# wi-fi.net
KiCad netlist of a schematic drawn in Altium Designer
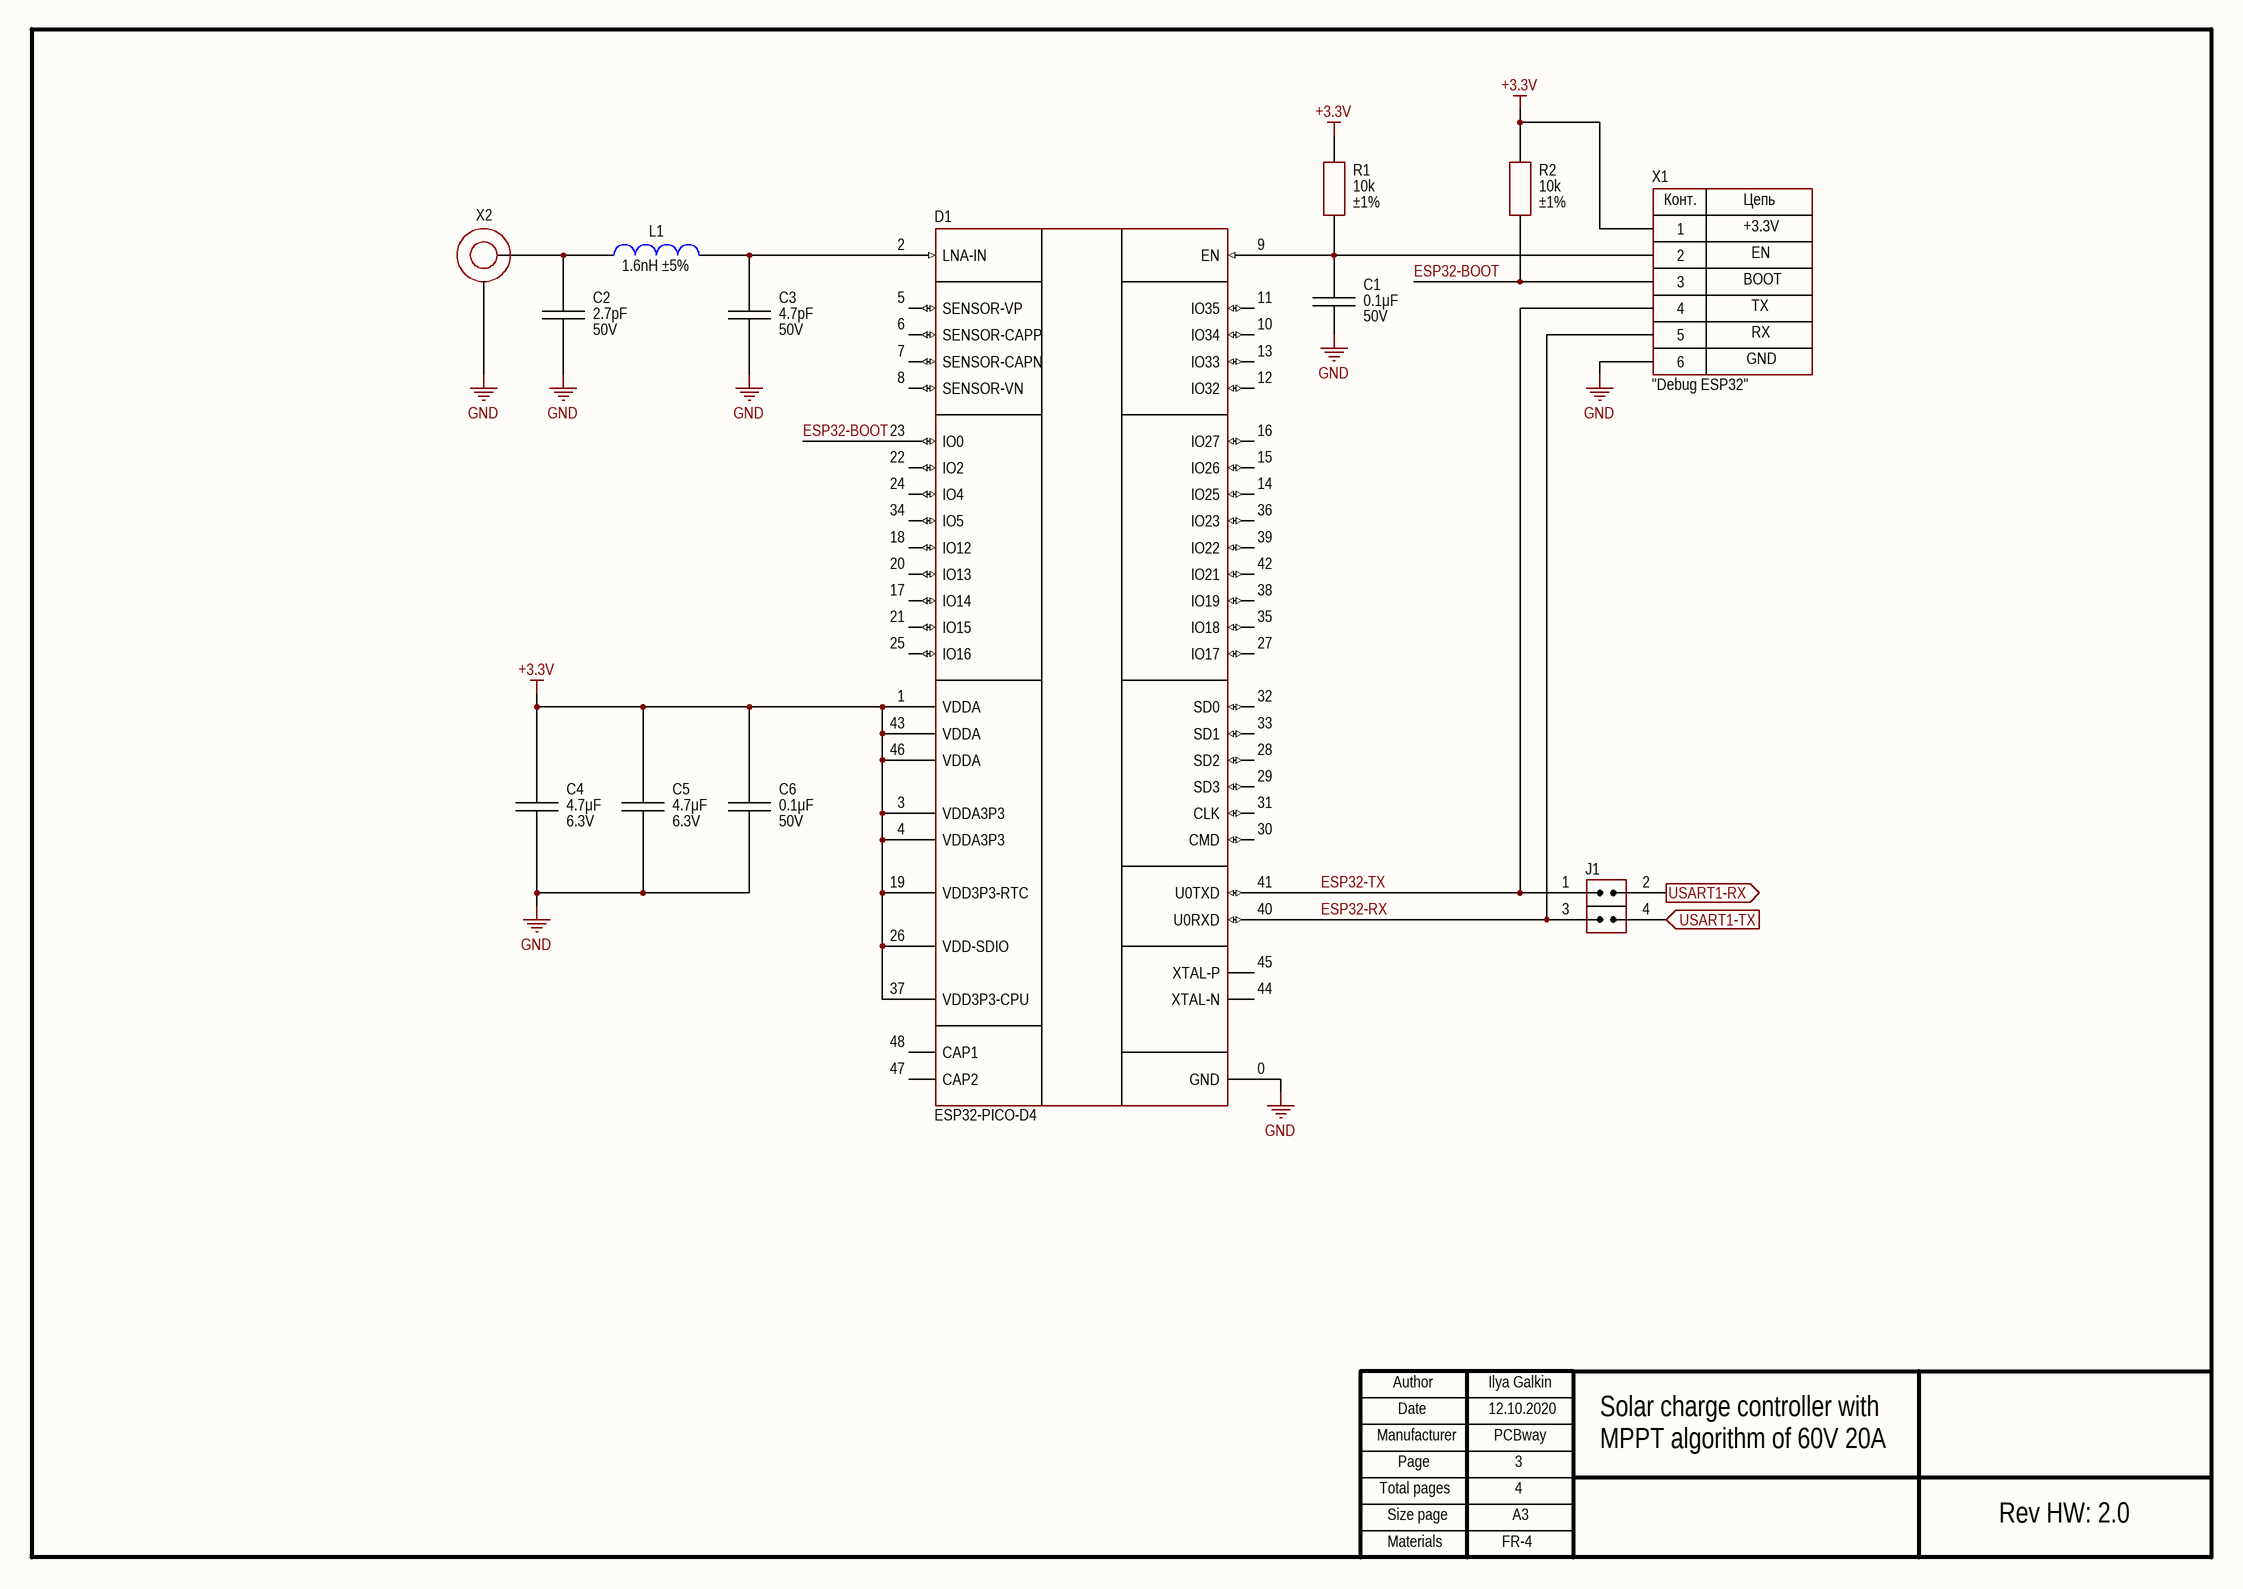
[diagram p0: wi-fi.SchDoc]

(export (version "E")
  (design (tool "Eeschema 10.0.6"))
  (components
    (comp (ref "C1")
      (value "0.1μF")
      (footprint "CAP: 0603")
      (fields
        (field (name "MANUFACTURER") "Samsung")
        (field (name "PARTNUMBER") "CL10B104KB8WPND")
        (field (name "VALUEMANUFACTURERPARTNUMBER") "Ceramic capacitor, 0.1μF, X7R, ±10%, 50V, 0603, -55...+125°C")
        (field (name "VOLTAGE") "50V")
      )
      (libsource (lib "Capacitor") (part "Ceramic_0603"))
    )
    (comp (ref "C2")
      (value "2.7pF")
      (footprint "CAP: 0603")
      (fields
        (field (name "MANUFACTURER") "Samsung")
        (field (name "PARTNUMBER") "CL10C2R7CB81PNC")
        (field (name "VALUEMANUFACTURERPARTNUMBER") "Ceramic capacitor, 2.7pF, NPO, ±0.25pF, 50V, 0603, -55...+125°C")
        (field (name "VOLTAGE") "50V")
      )
      (libsource (lib "capacitor") (part "Ceramic_0603"))
    )
    (comp (ref "C3")
      (value "4.7pF")
      (footprint "CAP: 0603")
      (fields
        (field (name "MANUFACTURER") "Samsung")
        (field (name "PARTNUMBER") "CL10C4R7BB8NNNC")
        (field (name "VALUEMANUFACTURERPARTNUMBER") "Ceramic capacitor, 4.7pF, NPO, ±0.1pF, 50V, 0603, -55...+125°C")
        (field (name "VOLTAGE") "50V")
      )
      (libsource (lib "capacitor") (part "Ceramic_0603"))
    )
    (comp (ref "C4")
      (value "4.7μF")
      (footprint "CAP: 0603")
      (fields
        (field (name "MANUFACTURER") "Samsung")
        (field (name "PARTNUMBER") "CL10B475KQ8NQNC")
        (field (name "VALUEMANUFACTURERPARTNUMBER") "Ceramic capacitor, 4.7μF, X7R, ±10%, 6.3V, 0603, -55...+125°C")
        (field (name "VOLTAGE") "6.3V")
      )
      (libsource (lib "Capacitor") (part "Ceramic_0603"))
    )
    (comp (ref "C5")
      (value "4.7μF")
      (footprint "CAP: 0603")
      (fields
        (field (name "MANUFACTURER") "Samsung")
        (field (name "PARTNUMBER") "CL10B475KQ8NQNC")
        (field (name "VALUEMANUFACTURERPARTNUMBER") "Ceramic capacitor, 4.7μF, X7R, ±10%, 6.3V, 0603, -55...+125°C")
        (field (name "VOLTAGE") "6.3V")
      )
      (libsource (lib "Capacitor") (part "Ceramic_0603"))
    )
    (comp (ref "C6")
      (value "0.1μF")
      (footprint "CAP: 0603")
      (fields
        (field (name "MANUFACTURER") "Samsung")
        (field (name "PARTNUMBER") "CL10B104KB8WPND")
        (field (name "VALUEMANUFACTURERPARTNUMBER") "Ceramic capacitor, 0.1μF, X7R, ±10%, 50V, 0603, -55...+125°C")
        (field (name "VOLTAGE") "50V")
      )
      (libsource (lib "Capacitor") (part "Ceramic_0603"))
    )
    (comp (ref "D1")
      (value "~")
      (footprint "48-LGA (7x7)")
      (description "Wi-Fi+BT")
      (fields (field (name "MANUFACTURER") "Espressif Systems") (field (name "PARTNUMBER") "ESP32-PICO-D4"))
      (libsource (lib "ic-rf-transceiver") (part "ESP32-PICO-D4"))
    )
    (comp (ref "J1")
      (value "~")
      (footprint "CON: JUMPER x2")
      (libsource (lib "connector") (part "Jumper_double"))
    )
    (comp (ref "L1")
      (value "1.6nH")
      (footprint "IND: 0603")
      (fields
        (field (name "MANUFACTURER") "Murata Electronics")
        (field (name "PARTNUMBER") "LQW18AS1N6J0ZD")
        (field (name "VALUEMANUFACTURERPARTNUMBER") "Fixed inductor, 1.6nH, ±5%, 0603, 700mA, -55...+125°C")
        (field (name "TOLERANCE") "±5%")
      )
      (libsource (lib "inductor") (part "Inductor_0603"))
    )
    (comp (ref "R1")
      (value "10k")
      (footprint "RES: 0603")
      (fields
        (field (name "MANUFACTURER") "Yageo")
        (field (name "PARTNUMBER") "AC0603FR-0710KL")
        (field (name "VALUEMANUFACTURERPARTNUMBER") "Resistor film, 10k, ±1%, 0603, 0.1W, -55...+125°C")
        (field (name "TOLERANCE") "±1%")
      )
      (libsource (lib "Resistor") (part "Resistor_0603"))
    )
    (comp (ref "R2")
      (value "10k")
      (footprint "RES: 0603")
      (fields
        (field (name "MANUFACTURER") "Yageo")
        (field (name "PARTNUMBER") "AC0603FR-0710KL")
        (field (name "VALUEMANUFACTURERPARTNUMBER") "Resistor film, 10k, ±1%, 0603, 0.1W, -55...+125°C")
        (field (name "TOLERANCE") "±1%")
      )
      (libsource (lib "Resistor") (part "Resistor_0603"))
    )
    (comp (ref "X1")
      (value "~")
      (footprint "CON: SM06B-GHS")
      (fields
        (field (name "MANUFACTURER") "JST")
        (field (name "VALUEMANUFACTURERPARTNUMBER") "Connector, 6pin, 1.25mm, 50VDC, 1A")
        (field (name "PARTNUMBER") "SM06B-GHS")
        (field (name "COMMENTTEXT") "\"Debug ESP32\"")
      )
      (libsource (lib "connector") (part "Connector_SM06B"))
    )
    (comp (ref "X2")
      (value "~")
      (footprint "CON: SMA")
      (fields
        (field (name "MANUFACTURER") "TE Connectivity")
        (field (name "VALUEMANUFACTURERPARTNUMBER") "Connector SMA, 50 Ohm, 3GHz")
        (field (name "PARTNUMBER") "5-1814832-1")
      )
      (libsource (lib "connector") (part "Connector_SMA"))
    )
  )
  (nets
    (net (code "1") (name "+3.3V") (class "Default")
      (node (ref "C4") (pin "2") (pinfunction "2_2") (pintype "power_in"))
      (node (ref "C5") (pin "2") (pinfunction "2_2") (pintype "power_in"))
      (node (ref "C6") (pin "2") (pinfunction "2_2") (pintype "power_in"))
      (node (ref "D1") (pin "1") (pinfunction "VDDA_1") (pintype "passive"))
      (node (ref "D1") (pin "19") (pinfunction "VDD3P3-RTC_19") (pintype "passive"))
      (node (ref "D1") (pin "26") (pinfunction "VDD-SDIO_26") (pintype "passive"))
      (node (ref "D1") (pin "3") (pinfunction "VDDA3P3_3") (pintype "passive"))
      (node (ref "D1") (pin "37") (pinfunction "VDD3P3-CPU_37") (pintype "passive"))
      (node (ref "D1") (pin "4") (pinfunction "VDDA3P3_4") (pintype "passive"))
      (node (ref "D1") (pin "43") (pinfunction "VDDA_43") (pintype "passive"))
      (node (ref "D1") (pin "46") (pinfunction "VDDA_46") (pintype "passive"))
      (node (ref "R1") (pin "2") (pinfunction "2_2") (pintype "passive"))
      (node (ref "R2") (pin "2") (pinfunction "2_2") (pintype "passive"))
      (node (ref "X1") (pin "1") (pinfunction "1_1") (pintype "passive"))
    )
    (net (code "2") (name "/ESP32-BOOT") (class "Default")
      (node (ref "D1") (pin "23") (pinfunction "IO0_23") (pintype "bidirectional"))
      (node (ref "R2") (pin "1") (pinfunction "1_1") (pintype "passive"))
      (node (ref "X1") (pin "3") (pinfunction "3_3") (pintype "power_in"))
    )
    (net (code "3") (name "/ESP32-RX") (class "Default")
      (node (ref "D1") (pin "40") (pinfunction "U0RXD_40") (pintype "bidirectional"))
      (node (ref "J1") (pin "3") (pinfunction "IN_3") (pintype "passive"))
      (node (ref "X1") (pin "5") (pinfunction "5_5") (pintype "power_in"))
    )
    (net (code "4") (name "/ESP32-TX") (class "Default")
      (node (ref "D1") (pin "41") (pinfunction "U0TXD_41") (pintype "bidirectional"))
      (node (ref "J1") (pin "1") (pinfunction "IN_1") (pintype "passive"))
      (node (ref "X1") (pin "4") (pinfunction "4_4") (pintype "power_in"))
    )
    (net (code "5") (name "/USART1-RX") (class "Default")
      (node (ref "J1") (pin "2") (pinfunction "IN_2") (pintype "passive"))
    )
    (net (code "6") (name "/USART1-TX") (class "Default")
      (node (ref "J1") (pin "4") (pinfunction "IN_4") (pintype "passive"))
    )
    (net (code "7") (name "GND") (class "Default")
      (node (ref "C1") (pin "1") (pinfunction "1_1") (pintype "power_in"))
      (node (ref "C2") (pin "1") (pinfunction "1_1") (pintype "passive"))
      (node (ref "C3") (pin "1") (pinfunction "1_1") (pintype "passive"))
      (node (ref "C4") (pin "1") (pinfunction "1_1") (pintype "power_in"))
      (node (ref "C5") (pin "1") (pinfunction "1_1") (pintype "power_in"))
      (node (ref "C6") (pin "1") (pinfunction "1_1") (pintype "power_in"))
      (node (ref "D1") (pin "0") (pinfunction "GND_0") (pintype "passive"))
      (node (ref "X1") (pin "6") (pinfunction "6_6") (pintype "power_in"))
      (node (ref "X2") (pin "2") (pinfunction "2_2") (pintype "passive"))
    )
    (net (code "8") (name "Net-(C2-Pad2)") (class "Default")
      (node (ref "C2") (pin "2") (pinfunction "2_2") (pintype "passive"))
      (node (ref "L1") (pin "2") (pinfunction "2_2") (pintype "passive"))
      (node (ref "X2") (pin "1") (pinfunction "1_1") (pintype "passive"))
    )
    (net (code "9") (name "Net-(D1-EN)") (class "Default")
      (node (ref "C1") (pin "2") (pinfunction "2_2") (pintype "power_in"))
      (node (ref "D1") (pin "9") (pinfunction "EN_9") (pintype "input"))
      (node (ref "R1") (pin "1") (pinfunction "1_1") (pintype "passive"))
      (node (ref "X1") (pin "2") (pinfunction "2_2") (pintype "passive"))
    )
    (net (code "10") (name "Net-(D1-LNA-IN)") (class "Default")
      (node (ref "C3") (pin "2") (pinfunction "2_2") (pintype "passive"))
      (node (ref "D1") (pin "2") (pinfunction "LNA-IN_2") (pintype "input"))
      (node (ref "L1") (pin "1") (pinfunction "1_1") (pintype "passive"))
    )
    (net (code "11") (name "unconnected-(D1-CAP1-Pad48)") (class "Default")
      (node (ref "D1") (pin "48") (pinfunction "CAP1_48") (pintype "passive"))
    )
    (net (code "12") (name "unconnected-(D1-CAP2-Pad47)") (class "Default")
      (node (ref "D1") (pin "47") (pinfunction "CAP2_47") (pintype "passive"))
    )
    (net (code "13") (name "unconnected-(D1-CLK-Pad31)") (class "Default")
      (node (ref "D1") (pin "31") (pinfunction "CLK_31") (pintype "bidirectional"))
    )
    (net (code "14") (name "unconnected-(D1-CMD-Pad30)") (class "Default")
      (node (ref "D1") (pin "30") (pinfunction "CMD_30") (pintype "bidirectional"))
    )
    (net (code "15") (name "unconnected-(D1-IO2-Pad22)") (class "Default")
      (node (ref "D1") (pin "22") (pinfunction "IO2_22") (pintype "bidirectional"))
    )
    (net (code "16") (name "unconnected-(D1-IO4-Pad24)") (class "Default")
      (node (ref "D1") (pin "24") (pinfunction "IO4_24") (pintype "bidirectional"))
    )
    (net (code "17") (name "unconnected-(D1-IO5-Pad34)") (class "Default")
      (node (ref "D1") (pin "34") (pinfunction "IO5_34") (pintype "bidirectional"))
    )
    (net (code "18") (name "unconnected-(D1-IO12-Pad18)") (class "Default")
      (node (ref "D1") (pin "18") (pinfunction "IO12_18") (pintype "bidirectional"))
    )
    (net (code "19") (name "unconnected-(D1-IO13-Pad20)") (class "Default")
      (node (ref "D1") (pin "20") (pinfunction "IO13_20") (pintype "bidirectional"))
    )
    (net (code "20") (name "unconnected-(D1-IO14-Pad17)") (class "Default")
      (node (ref "D1") (pin "17") (pinfunction "IO14_17") (pintype "bidirectional"))
    )
    (net (code "21") (name "unconnected-(D1-IO15-Pad21)") (class "Default")
      (node (ref "D1") (pin "21") (pinfunction "IO15_21") (pintype "bidirectional"))
    )
    (net (code "22") (name "unconnected-(D1-IO16-Pad25)") (class "Default")
      (node (ref "D1") (pin "25") (pinfunction "IO16_25") (pintype "bidirectional"))
    )
    (net (code "23") (name "unconnected-(D1-IO17-Pad27)") (class "Default")
      (node (ref "D1") (pin "27") (pinfunction "IO17_27") (pintype "bidirectional"))
    )
    (net (code "24") (name "unconnected-(D1-IO18-Pad35)") (class "Default")
      (node (ref "D1") (pin "35") (pinfunction "IO18_35") (pintype "bidirectional"))
    )
    (net (code "25") (name "unconnected-(D1-IO19-Pad38)") (class "Default")
      (node (ref "D1") (pin "38") (pinfunction "IO19_38") (pintype "bidirectional"))
    )
    (net (code "26") (name "unconnected-(D1-IO21-Pad42)") (class "Default")
      (node (ref "D1") (pin "42") (pinfunction "IO21_42") (pintype "bidirectional"))
    )
    (net (code "27") (name "unconnected-(D1-IO22-Pad39)") (class "Default")
      (node (ref "D1") (pin "39") (pinfunction "IO22_39") (pintype "bidirectional"))
    )
    (net (code "28") (name "unconnected-(D1-IO23-Pad36)") (class "Default")
      (node (ref "D1") (pin "36") (pinfunction "IO23_36") (pintype "bidirectional"))
    )
    (net (code "29") (name "unconnected-(D1-IO25-Pad14)") (class "Default")
      (node (ref "D1") (pin "14") (pinfunction "IO25_14") (pintype "bidirectional"))
    )
    (net (code "30") (name "unconnected-(D1-IO26-Pad15)") (class "Default")
      (node (ref "D1") (pin "15") (pinfunction "IO26_15") (pintype "bidirectional"))
    )
    (net (code "31") (name "unconnected-(D1-IO27-Pad16)") (class "Default")
      (node (ref "D1") (pin "16") (pinfunction "IO27_16") (pintype "bidirectional"))
    )
    (net (code "32") (name "unconnected-(D1-IO32-Pad12)") (class "Default")
      (node (ref "D1") (pin "12") (pinfunction "IO32_12") (pintype "bidirectional"))
    )
    (net (code "33") (name "unconnected-(D1-IO33-Pad13)") (class "Default")
      (node (ref "D1") (pin "13") (pinfunction "IO33_13") (pintype "bidirectional"))
    )
    (net (code "34") (name "unconnected-(D1-IO34-Pad10)") (class "Default")
      (node (ref "D1") (pin "10") (pinfunction "IO34_10") (pintype "bidirectional"))
    )
    (net (code "35") (name "unconnected-(D1-IO35-Pad11)") (class "Default")
      (node (ref "D1") (pin "11") (pinfunction "IO35_11") (pintype "bidirectional"))
    )
    (net (code "36") (name "unconnected-(D1-SD0-Pad32)") (class "Default")
      (node (ref "D1") (pin "32") (pinfunction "SD0_32") (pintype "bidirectional"))
    )
    (net (code "37") (name "unconnected-(D1-SD1-Pad33)") (class "Default")
      (node (ref "D1") (pin "33") (pinfunction "SD1_33") (pintype "bidirectional"))
    )
    (net (code "38") (name "unconnected-(D1-SD2-Pad28)") (class "Default")
      (node (ref "D1") (pin "28") (pinfunction "SD2_28") (pintype "bidirectional"))
    )
    (net (code "39") (name "unconnected-(D1-SD3-Pad29)") (class "Default")
      (node (ref "D1") (pin "29") (pinfunction "SD3_29") (pintype "bidirectional"))
    )
    (net (code "40") (name "unconnected-(D1-SENSOR-CAPN-Pad7)") (class "Default")
      (node (ref "D1") (pin "7") (pinfunction "SENSOR-CAPN_7") (pintype "bidirectional"))
    )
    (net (code "41") (name "unconnected-(D1-SENSOR-CAPP-Pad6)") (class "Default")
      (node (ref "D1") (pin "6") (pinfunction "SENSOR-CAPP_6") (pintype "bidirectional"))
    )
    (net (code "42") (name "unconnected-(D1-SENSOR-VN-Pad8)") (class "Default")
      (node (ref "D1") (pin "8") (pinfunction "SENSOR-VN_8") (pintype "bidirectional"))
    )
    (net (code "43") (name "unconnected-(D1-SENSOR-VP-Pad5)") (class "Default")
      (node (ref "D1") (pin "5") (pinfunction "SENSOR-VP_5") (pintype "bidirectional"))
    )
    (net (code "44") (name "unconnected-(D1-XTAL-N-Pad44)") (class "Default")
      (node (ref "D1") (pin "44") (pinfunction "XTAL-N_44") (pintype "passive"))
    )
    (net (code "45") (name "unconnected-(D1-XTAL-P-Pad45)") (class "Default")
      (node (ref "D1") (pin "45") (pinfunction "XTAL-P_45") (pintype "passive"))
    )
  )
)
